# RN41Board.net
KiCad netlist of a schematic drawn in EAGLE
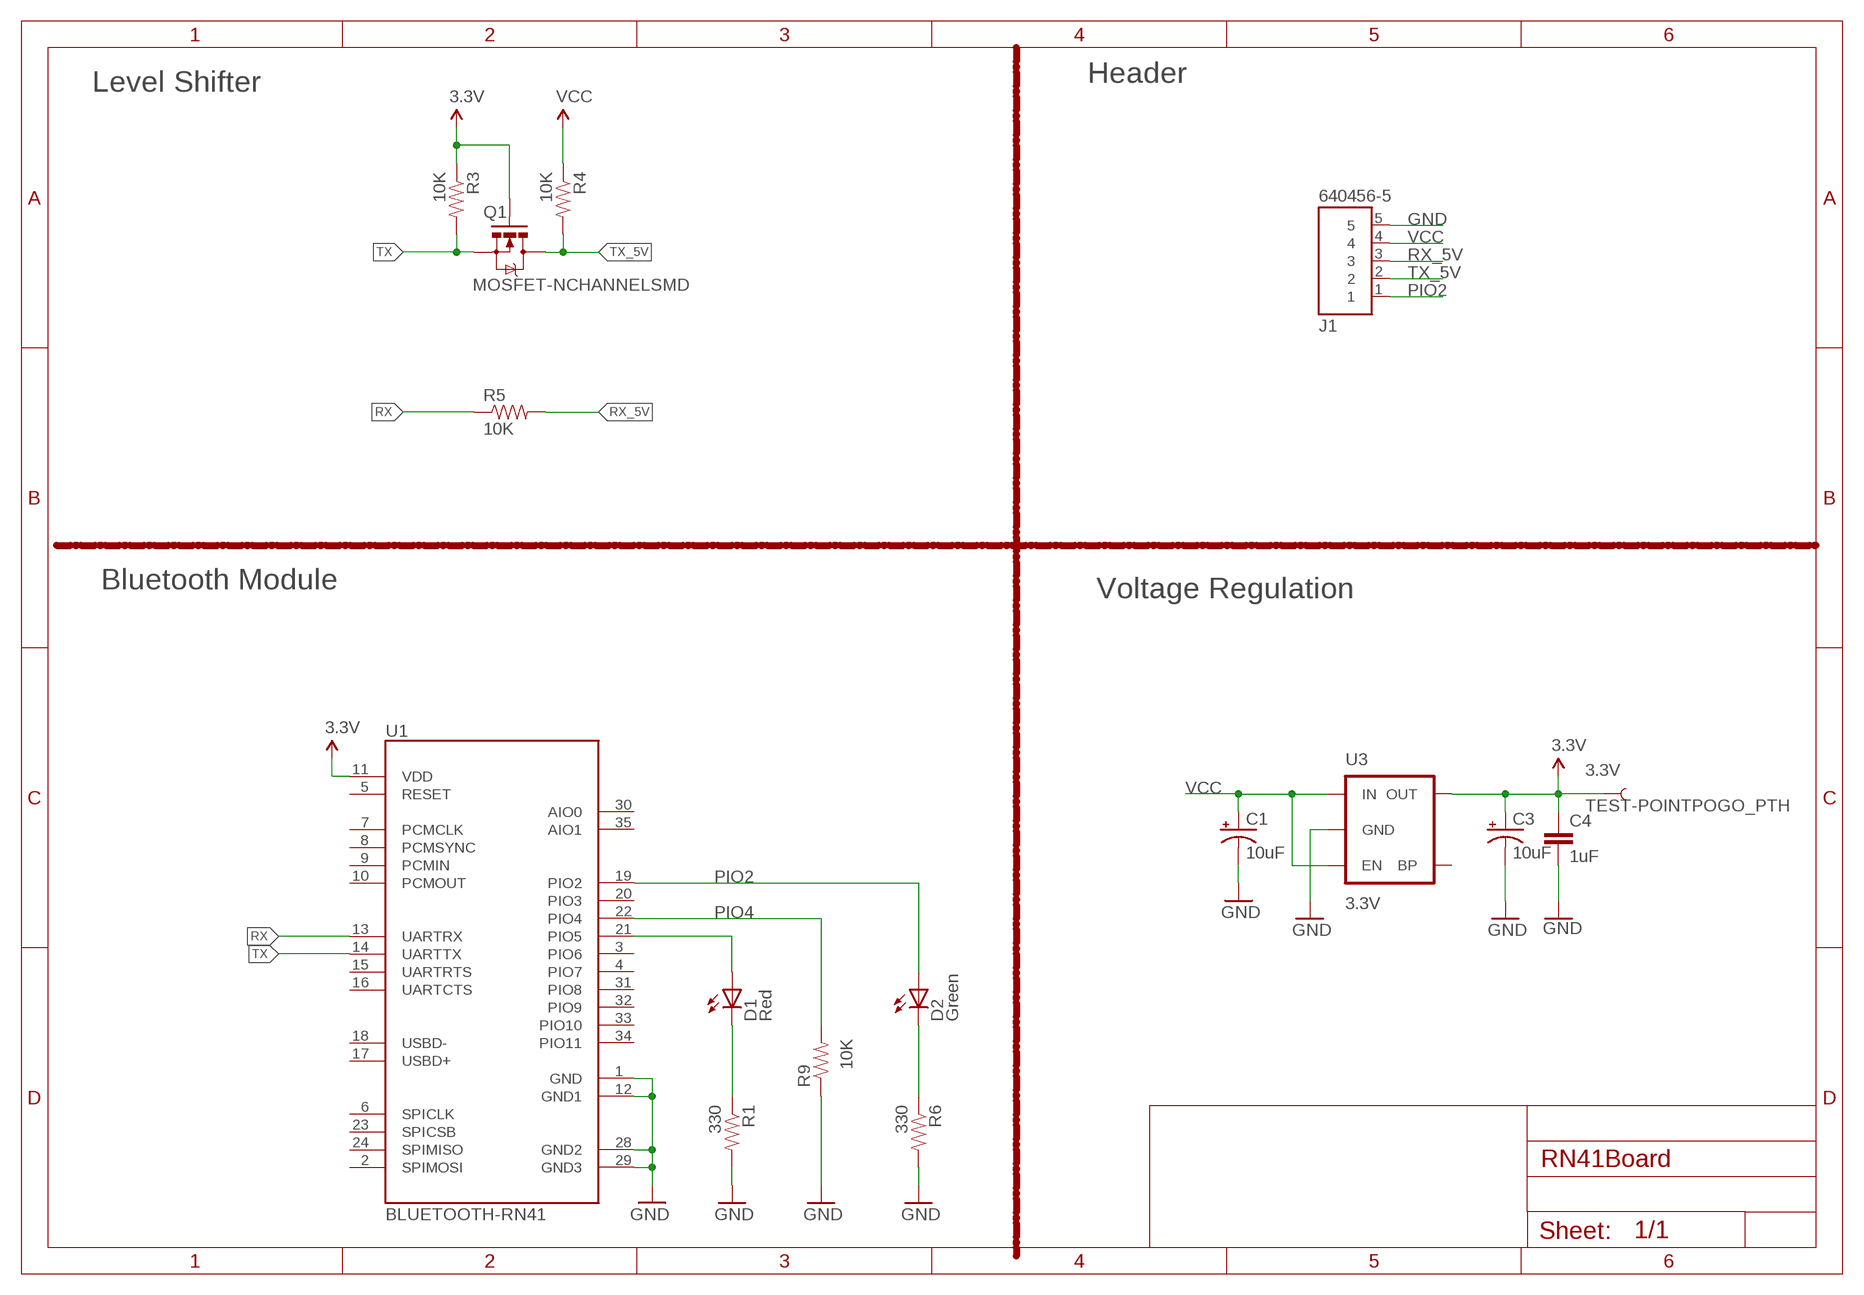
[diagram p0: schematic, sheet 1]

(export (version "E")
  (design (tool "Eeschema 10.0.6"))
  (components
    (comp (ref "3.3V")
      (value "TEST-POINTPOGO_PTH")
      (footprint "eagle-import:1X01_NO_SILK")
      (libsource (lib "eagle-import") (part "TEST-POINTPOGO_PTH"))
    )
    (comp (ref "C1")
      (value "10uF")
      (footprint "eagle-import:EIA3216")
      (libsource (lib "eagle-import") (part "CAP_POL1206"))
    )
    (comp (ref "C3")
      (value "10uF")
      (footprint "eagle-import:EIA3216")
      (libsource (lib "eagle-import") (part "CAP_POL1206"))
    )
    (comp (ref "C4")
      (value "1uF")
      (footprint "eagle-import:0603-CAP")
      (libsource (lib "eagle-import") (part "CAP0603-CAP"))
    )
    (comp (ref "D1")
      (value "Red")
      (footprint "eagle-import:LED-0603")
      (libsource (lib "eagle-import") (part "LED0603"))
    )
    (comp (ref "D2")
      (value "Green")
      (footprint "eagle-import:LED-0603")
      (libsource (lib "eagle-import") (part "LED0603"))
    )
    (comp (ref "J1")
      (value "640456-5")
      (footprint "eagle-import:TE_640456-5")
      (fields (field (name "DIGI-KEY_PART_NUMBER") "A19471-ND") (field (name "MF") "TE Connectivity"))
      (libsource (lib "eagle-import") (part "640456-5"))
    )
    (comp (ref "Q1")
      (value "MOSFET-NCHANNELSMD")
      (footprint "eagle-import:SOT23-3")
      (libsource (lib "eagle-import") (part "MOSFET-NCHANNELSMD"))
    )
    (comp (ref "R1")
      (value "330")
      (footprint "eagle-import:0603-RES")
      (libsource (lib "eagle-import") (part "RESISTOR0603-RES"))
    )
    (comp (ref "R3")
      (value "10K")
      (footprint "eagle-import:0603-RES")
      (libsource (lib "eagle-import") (part "RESISTOR0603-RES"))
    )
    (comp (ref "R4")
      (value "10K")
      (footprint "eagle-import:0603-RES")
      (libsource (lib "eagle-import") (part "RESISTOR0603-RES"))
    )
    (comp (ref "R5")
      (value "10K")
      (footprint "eagle-import:0603-RES")
      (libsource (lib "eagle-import") (part "RESISTOR0603-RES"))
    )
    (comp (ref "R6")
      (value "330")
      (footprint "eagle-import:0603-RES")
      (libsource (lib "eagle-import") (part "RESISTOR0603-RES"))
    )
    (comp (ref "R9")
      (value "10K")
      (footprint "eagle-import:0603-RES")
      (libsource (lib "eagle-import") (part "RESISTOR0603-RES"))
    )
    (comp (ref "U1")
      (value "BLUETOOTH-RN41")
      (footprint "eagle-import:RN41")
      (libsource (lib "eagle-import") (part "BLUETOOTH-RN41{dblquote}"))
    )
    (comp (ref "U3")
      (value "3.3V")
      (footprint "eagle-import:SOT23-5")
      (libsource (lib "eagle-import") (part "V_REG_LDOSMD"))
    )
  )
  (nets
    (net (code "1") (name "/PIO2") (class "Default")
      (node (ref "D2") (pin "A") (pinfunction "A_A") (pintype "passive"))
      (node (ref "J1") (pin "1") (pinfunction "1_1") (pintype "passive"))
      (node (ref "U1") (pin "19") (pinfunction "PIO2_19") (pintype "bidirectional"))
    )
    (net (code "2") (name "/PIO4") (class "Default")
      (node (ref "R9") (pin "2") (pinfunction "2_2") (pintype "passive"))
      (node (ref "U1") (pin "22") (pinfunction "PIO4_22") (pintype "bidirectional"))
    )
    (net (code "3") (name "3.3V") (class "Default")
      (node (ref "3.3V") (pin "1") (pinfunction "1_1") (pintype "bidirectional"))
      (node (ref "C3") (pin "A") (pinfunction "+_A") (pintype "passive"))
      (node (ref "C4") (pin "1") (pinfunction "1_1") (pintype "passive"))
      (node (ref "Q1") (pin "1") (pinfunction "G_1") (pintype "passive"))
      (node (ref "R3") (pin "1") (pinfunction "1_1") (pintype "passive"))
      (node (ref "U1") (pin "11") (pinfunction "VDD_11") (pintype "bidirectional"))
      (node (ref "U3") (pin "5") (pinfunction "OUT_5") (pintype "passive"))
    )
    (net (code "4") (name "GND") (class "Default")
      (node (ref "C1") (pin "C") (pinfunction "-_C") (pintype "passive"))
      (node (ref "C3") (pin "C") (pinfunction "-_C") (pintype "passive"))
      (node (ref "C4") (pin "2") (pinfunction "2_2") (pintype "passive"))
      (node (ref "J1") (pin "5") (pinfunction "5_5") (pintype "passive"))
      (node (ref "R1") (pin "2") (pinfunction "2_2") (pintype "passive"))
      (node (ref "R6") (pin "2") (pinfunction "2_2") (pintype "passive"))
      (node (ref "R9") (pin "1") (pinfunction "1_1") (pintype "passive"))
      (node (ref "U1") (pin "1") (pinfunction "GND_1") (pintype "bidirectional"))
      (node (ref "U1") (pin "12") (pinfunction "GND1_12") (pintype "bidirectional"))
      (node (ref "U1") (pin "28") (pinfunction "GND2_28") (pintype "bidirectional"))
      (node (ref "U1") (pin "29") (pinfunction "GND3_29") (pintype "bidirectional"))
      (node (ref "U3") (pin "2") (pinfunction "GND_2") (pintype "input"))
    )
    (net (code "5") (name "Net-(D1-PadC)") (class "Default")
      (node (ref "D1") (pin "C") (pinfunction "C_C") (pintype "passive"))
      (node (ref "R1") (pin "1") (pinfunction "1_1") (pintype "passive"))
    )
    (net (code "6") (name "Net-(D2-PadC)") (class "Default")
      (node (ref "D2") (pin "C") (pinfunction "C_C") (pintype "passive"))
      (node (ref "R6") (pin "1") (pinfunction "1_1") (pintype "passive"))
    )
    (net (code "7") (name "Net-(U1-PIO5)") (class "Default")
      (node (ref "D1") (pin "A") (pinfunction "A_A") (pintype "passive"))
      (node (ref "U1") (pin "21") (pinfunction "PIO5_21") (pintype "bidirectional"))
    )
    (net (code "8") (name "RX") (class "Default")
      (node (ref "R5") (pin "1") (pinfunction "1_1") (pintype "passive"))
      (node (ref "U1") (pin "13") (pinfunction "UARTRX_13") (pintype "bidirectional"))
    )
    (net (code "9") (name "RX_5V") (class "Default")
      (node (ref "J1") (pin "3") (pinfunction "3_3") (pintype "passive"))
      (node (ref "R5") (pin "2") (pinfunction "2_2") (pintype "passive"))
    )
    (net (code "10") (name "TX") (class "Default")
      (node (ref "Q1") (pin "2") (pinfunction "S_2") (pintype "passive"))
      (node (ref "R3") (pin "2") (pinfunction "2_2") (pintype "passive"))
      (node (ref "U1") (pin "14") (pinfunction "UARTTX_14") (pintype "bidirectional"))
    )
    (net (code "11") (name "TX_5V") (class "Default")
      (node (ref "J1") (pin "2") (pinfunction "2_2") (pintype "passive"))
      (node (ref "Q1") (pin "3") (pinfunction "D_3") (pintype "passive"))
      (node (ref "R4") (pin "2") (pinfunction "2_2") (pintype "passive"))
    )
    (net (code "12") (name "VCC") (class "Default")
      (node (ref "C1") (pin "A") (pinfunction "+_A") (pintype "passive"))
      (node (ref "J1") (pin "4") (pinfunction "4_4") (pintype "passive"))
      (node (ref "R4") (pin "1") (pinfunction "1_1") (pintype "passive"))
      (node (ref "U3") (pin "1") (pinfunction "IN_1") (pintype "input"))
      (node (ref "U3") (pin "3") (pinfunction "EN_3") (pintype "input"))
    )
    (net (code "13") (name "unconnected-(U1-AIO0-Pad30)") (class "Default")
      (node (ref "U1") (pin "30") (pinfunction "AIO0_30") (pintype "bidirectional"))
    )
    (net (code "14") (name "unconnected-(U1-AIO1-Pad35)") (class "Default")
      (node (ref "U1") (pin "35") (pinfunction "AIO1_35") (pintype "bidirectional"))
    )
    (net (code "15") (name "unconnected-(U1-PCMCLK-Pad7)") (class "Default")
      (node (ref "U1") (pin "7") (pinfunction "PCMCLK_7") (pintype "bidirectional"))
    )
    (net (code "16") (name "unconnected-(U1-PCMIN-Pad9)") (class "Default")
      (node (ref "U1") (pin "9") (pinfunction "PCMIN_9") (pintype "bidirectional"))
    )
    (net (code "17") (name "unconnected-(U1-PCMOUT-Pad10)") (class "Default")
      (node (ref "U1") (pin "10") (pinfunction "PCMOUT_10") (pintype "bidirectional"))
    )
    (net (code "18") (name "unconnected-(U1-PCMSYNC-Pad8)") (class "Default")
      (node (ref "U1") (pin "8") (pinfunction "PCMSYNC_8") (pintype "bidirectional"))
    )
    (net (code "19") (name "unconnected-(U1-PIO3-Pad20)") (class "Default")
      (node (ref "U1") (pin "20") (pinfunction "PIO3_20") (pintype "bidirectional"))
    )
    (net (code "20") (name "unconnected-(U1-PIO6-Pad3)") (class "Default")
      (node (ref "U1") (pin "3") (pinfunction "PIO6_3") (pintype "bidirectional"))
    )
    (net (code "21") (name "unconnected-(U1-PIO7-Pad4)") (class "Default")
      (node (ref "U1") (pin "4") (pinfunction "PIO7_4") (pintype "bidirectional"))
    )
    (net (code "22") (name "unconnected-(U1-PIO8-Pad31)") (class "Default")
      (node (ref "U1") (pin "31") (pinfunction "PIO8_31") (pintype "bidirectional"))
    )
    (net (code "23") (name "unconnected-(U1-PIO9-Pad32)") (class "Default")
      (node (ref "U1") (pin "32") (pinfunction "PIO9_32") (pintype "bidirectional"))
    )
    (net (code "24") (name "unconnected-(U1-PIO10-Pad33)") (class "Default")
      (node (ref "U1") (pin "33") (pinfunction "PIO10_33") (pintype "bidirectional"))
    )
    (net (code "25") (name "unconnected-(U1-PIO11-Pad34)") (class "Default")
      (node (ref "U1") (pin "34") (pinfunction "PIO11_34") (pintype "bidirectional"))
    )
    (net (code "26") (name "unconnected-(U1-RESET-Pad5)") (class "Default")
      (node (ref "U1") (pin "5") (pinfunction "RESET_5") (pintype "bidirectional"))
    )
    (net (code "27") (name "unconnected-(U1-SPICLK-Pad6)") (class "Default")
      (node (ref "U1") (pin "6") (pinfunction "SPICLK_6") (pintype "bidirectional"))
    )
    (net (code "28") (name "unconnected-(U1-SPICSB-Pad23)") (class "Default")
      (node (ref "U1") (pin "23") (pinfunction "SPICSB_23") (pintype "bidirectional"))
    )
    (net (code "29") (name "unconnected-(U1-SPIMISO-Pad24)") (class "Default")
      (node (ref "U1") (pin "24") (pinfunction "SPIMISO_24") (pintype "bidirectional"))
    )
    (net (code "30") (name "unconnected-(U1-SPIMOSI-Pad2)") (class "Default")
      (node (ref "U1") (pin "2") (pinfunction "SPIMOSI_2") (pintype "bidirectional"))
    )
    (net (code "31") (name "unconnected-(U1-UARTCTS-Pad16)") (class "Default")
      (node (ref "U1") (pin "16") (pinfunction "UARTCTS_16") (pintype "bidirectional"))
    )
    (net (code "32") (name "unconnected-(U1-UARTRTS-Pad15)") (class "Default")
      (node (ref "U1") (pin "15") (pinfunction "UARTRTS_15") (pintype "bidirectional"))
    )
    (net (code "33") (name "unconnected-(U1-USBD+-Pad17)") (class "Default")
      (node (ref "U1") (pin "17") (pinfunction "USBD+_17") (pintype "bidirectional"))
    )
    (net (code "34") (name "unconnected-(U1-USBD--Pad18)") (class "Default")
      (node (ref "U1") (pin "18") (pinfunction "USBD-_18") (pintype "bidirectional"))
    )
    (net (code "35") (name "unconnected-(U3-BP-Pad4)") (class "Default")
      (node (ref "U3") (pin "4") (pinfunction "BP_4") (pintype "input"))
    )
  )
)
